# flprog.net
KiCad netlist of a schematic drawn in EAGLE
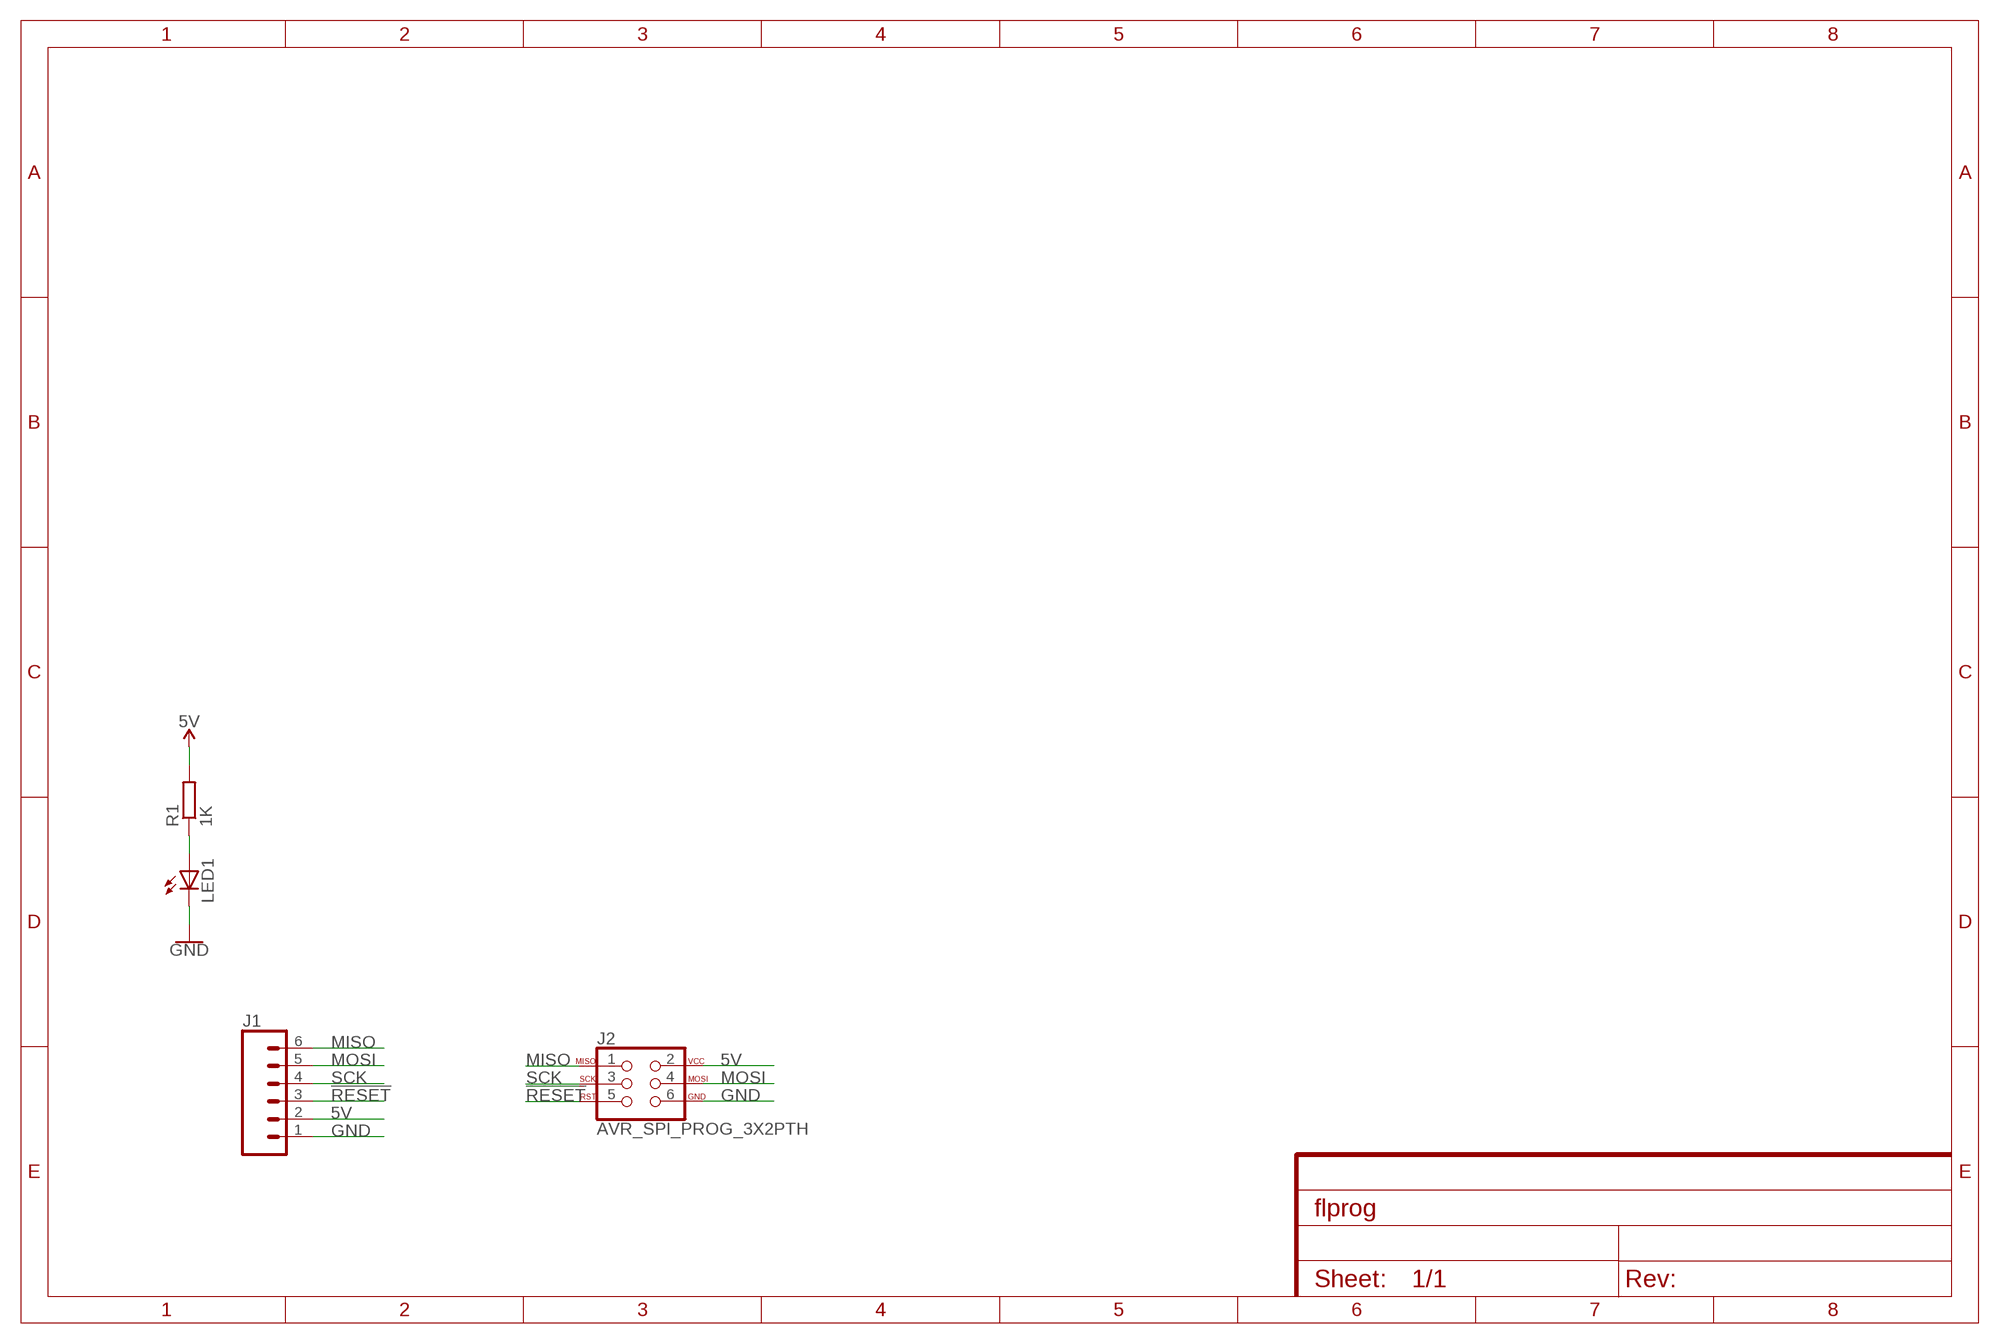
[diagram p0: schematic, sheet 1]

(export (version "E")
  (design (tool "Eeschema 10.0.6"))
  (components
    (comp (ref "J1")
      (value "CONN_06SMD-1MM")
      (footprint "eagle-import:1X06-1MM")
      (libsource (lib "eagle-import") (part "CONN_06SMD-1MM"))
    )
    (comp (ref "J2")
      (value "AVR_SPI_PROG_3X2PTH")
      (footprint "eagle-import:2X3")
      (libsource (lib "eagle-import") (part "AVR_SPI_PROG_3X2PTH"))
    )
    (comp (ref "LED1")
      (value "LEDCHIPLED_0603")
      (footprint "eagle-import:CHIPLED_0603")
      (libsource (lib "eagle-import") (part "LEDCHIPLED_0603"))
    )
    (comp (ref "R1")
      (value "1K")
      (footprint "eagle-import:R0603")
      (libsource (lib "eagle-import") (part "R-EU_R0603"))
    )
  )
  (nets
    (net (code "1") (name "/MISO") (class "Default")
      (node (ref "J1") (pin "6") (pinfunction "6_6") (pintype "passive"))
      (node (ref "J2") (pin "1") (pinfunction "1_1") (pintype "passive"))
    )
    (net (code "2") (name "/MOSI") (class "Default")
      (node (ref "J1") (pin "5") (pinfunction "5_5") (pintype "passive"))
      (node (ref "J2") (pin "4") (pinfunction "4_4") (pintype "passive"))
    )
    (net (code "3") (name "/SCK") (class "Default")
      (node (ref "J1") (pin "4") (pinfunction "4_4") (pintype "passive"))
      (node (ref "J2") (pin "3") (pinfunction "3_3") (pintype "passive"))
    )
    (net (code "4") (name "/~{RESET}") (class "Default")
      (node (ref "J1") (pin "3") (pinfunction "3_3") (pintype "passive"))
      (node (ref "J2") (pin "5") (pinfunction "5_5") (pintype "passive"))
    )
    (net (code "5") (name "5V") (class "Default")
      (node (ref "J1") (pin "2") (pinfunction "2_2") (pintype "passive"))
      (node (ref "J2") (pin "2") (pinfunction "2_2") (pintype "passive"))
      (node (ref "R1") (pin "2") (pinfunction "2_2") (pintype "passive"))
    )
    (net (code "6") (name "GND") (class "Default")
      (node (ref "J1") (pin "1") (pinfunction "1_1") (pintype "passive"))
      (node (ref "J2") (pin "6") (pinfunction "6_6") (pintype "passive"))
      (node (ref "LED1") (pin "C") (pinfunction "C_C") (pintype "passive"))
    )
    (net (code "7") (name "Net-(LED1-PadA)") (class "Default")
      (node (ref "LED1") (pin "A") (pinfunction "A_A") (pintype "passive"))
      (node (ref "R1") (pin "1") (pinfunction "1_1") (pintype "passive"))
    )
  )
)
